# lab2_lyaptsev_buck.net
KiCad netlist of a schematic drawn in Altium Designer
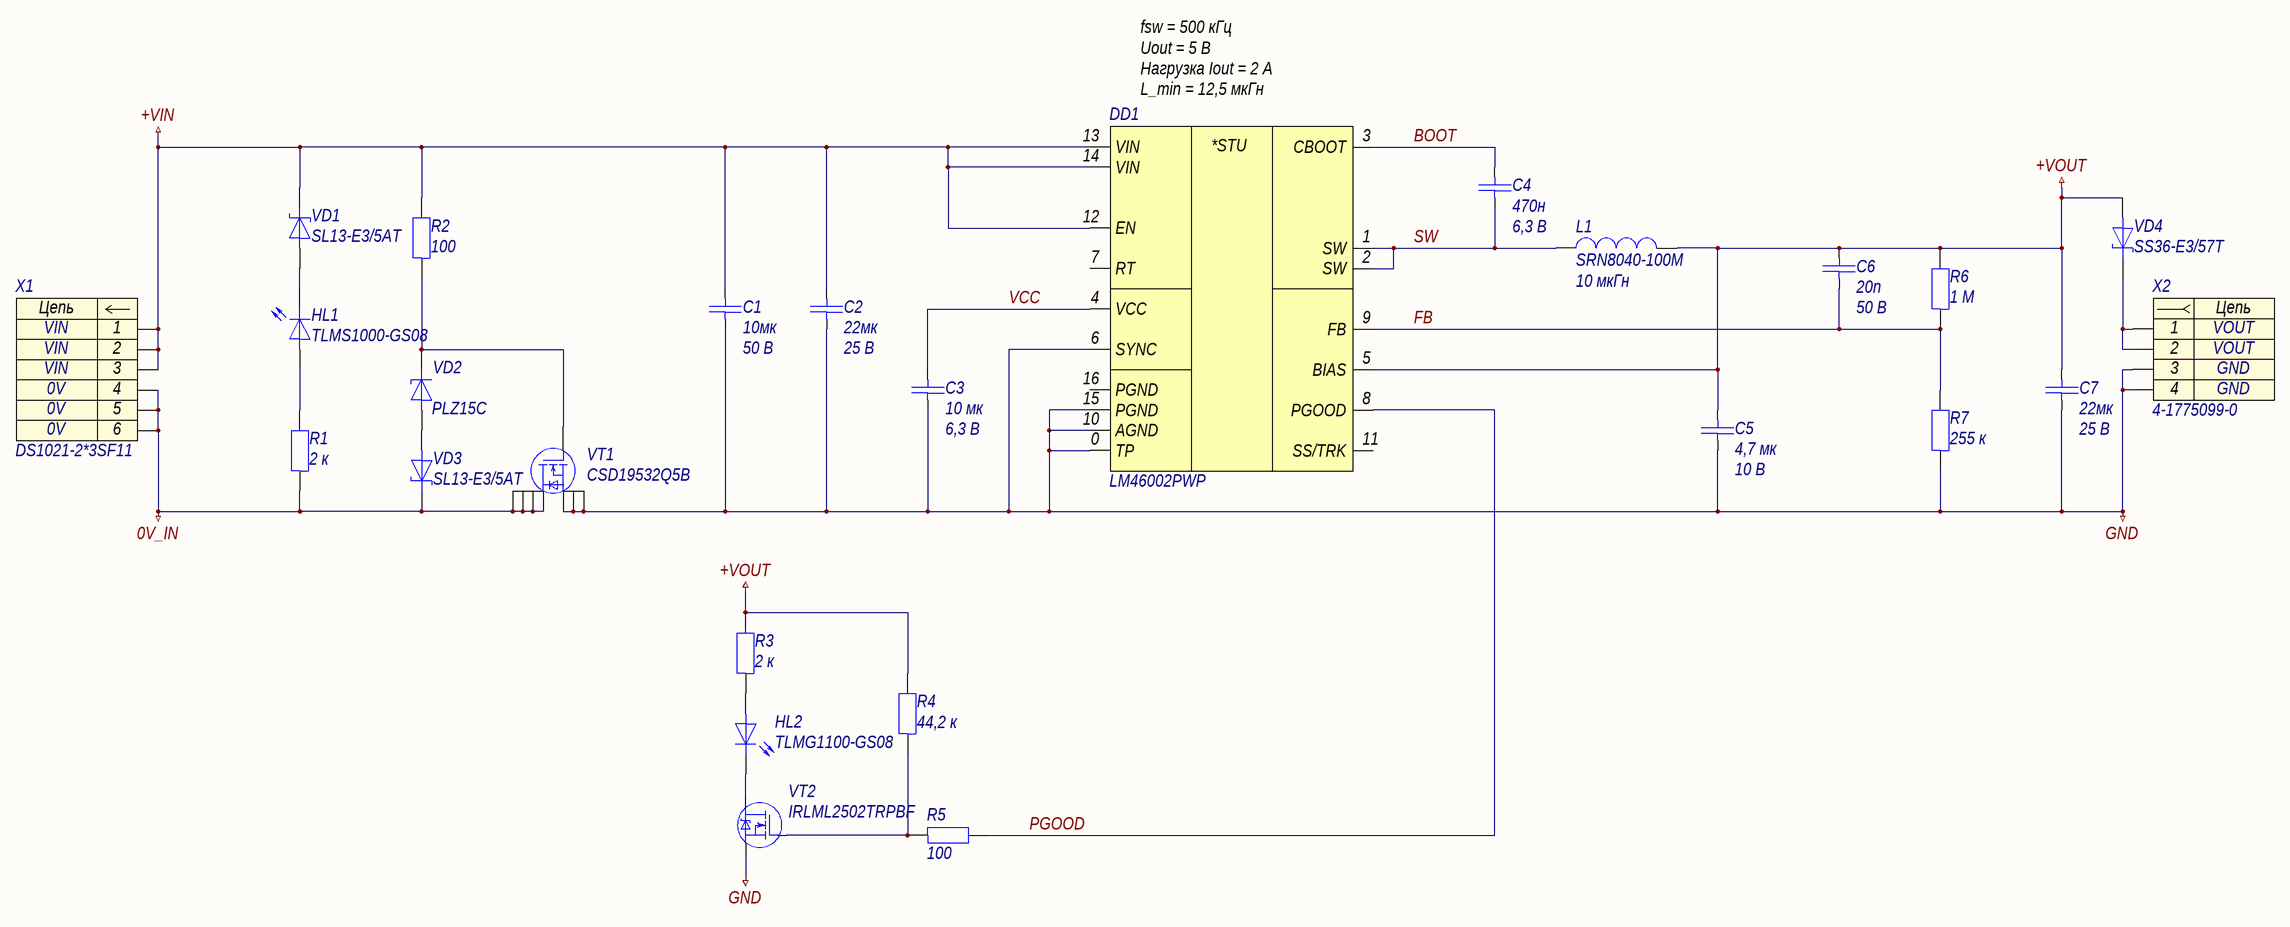
[diagram p0: lab2_lyaptsev_buck.SchDoc]

(export (version "E")
  (design (tool "Eeschema 10.0.6"))
  (components
    (comp (ref "C1")
      (value "10мк")
      (footprint "C1210")
      (description "=Описание")
      (fields (field (name "НАПРЯЖЕНИЕ") "50 В"))
      (libsource (lib "Database_Students_v1") (part "C-NONPOLAR"))
    )
    (comp (ref "C2")
      (value "22мк")
      (footprint "C1210")
      (description "=Описание")
      (fields (field (name "НАПРЯЖЕНИЕ") "25 В"))
      (libsource (lib "Database_Students_v1") (part "C-NONPOLAR"))
    )
    (comp (ref "C3")
      (value "10 мк")
      (footprint "C0603")
      (description "=Описание")
      (fields (field (name "НАПРЯЖЕНИЕ") "6,3 В"))
      (libsource (lib "Database_Students_v1") (part "C-NONPOLAR"))
    )
    (comp (ref "C4")
      (value "470н")
      (footprint "C0402")
      (description "=Описание")
      (fields (field (name "НАПРЯЖЕНИЕ") "6,3 В"))
      (libsource (lib "Database_Students_v1") (part "C-NONPOLAR"))
    )
    (comp (ref "C5")
      (value "4,7 мк")
      (footprint "C0805")
      (description "=Описание")
      (fields (field (name "НАПРЯЖЕНИЕ") "10 В"))
      (libsource (lib "Database_Students_v1") (part "C-NONPOLAR"))
    )
    (comp (ref "C6")
      (value "20п")
      (footprint "C0402")
      (description "=Описание")
      (fields (field (name "НАПРЯЖЕНИЕ") "50 В"))
      (libsource (lib "Database_Students_v1") (part "C-NONPOLAR"))
    )
    (comp (ref "C7")
      (value "22мк")
      (footprint "C1210")
      (description "=Описание")
      (fields (field (name "НАПРЯЖЕНИЕ") "25 В"))
      (libsource (lib "Database_Students_v1") (part "C-NONPOLAR"))
    )
    (comp (ref "DD1")
      (value "LM46002PWP")
      (footprint "HTSSOP-16")
      (description "=Описание")
      (libsource (lib "Database_Students") (part "LM46002PWP"))
    )
    (comp (ref "HL1")
      (value "TLMS1000-GS08")
      (footprint "HL0603")
      (description "=Описание")
      (libsource (lib "Database_Students") (part "HL-COMMON"))
    )
    (comp (ref "HL2")
      (value "TLMG1100-GS08")
      (footprint "HL0603")
      (description "=Описание")
      (libsource (lib "Database_Students") (part "HL-COMMON"))
    )
    (comp (ref "L1")
      (value "SRN8040-100M")
      (footprint "SRN-2-815X790X400")
      (description "=Описание")
      (fields (field (name "ИНДУКТИВНОСТЬ") "10 мкГн"))
      (libsource (lib "Database_Students") (part "INDUCTOR-COMMON"))
    )
    (comp (ref "R1")
      (value "2 к")
      (footprint "R0603")
      (description "=Описание")
      (libsource (lib "Database_Students") (part "R-COMMON"))
    )
    (comp (ref "R2")
      (value "100")
      (footprint "R0603")
      (description "=Описание")
      (libsource (lib "Database_Students") (part "R-COMMON"))
    )
    (comp (ref "R3")
      (value "2 к")
      (footprint "R0603")
      (description "=Описание")
      (libsource (lib "Database_Students") (part "R-COMMON"))
    )
    (comp (ref "R4")
      (value "44,2 к")
      (footprint "R0603")
      (description "=Описание")
      (libsource (lib "Database_Students") (part "R-COMMON"))
    )
    (comp (ref "R5")
      (value "100")
      (footprint "R0603")
      (description "=Описание")
      (libsource (lib "Database_Students") (part "R-COMMON"))
    )
    (comp (ref "R6")
      (value "1 М")
      (footprint "R0603")
      (description "=Описание")
      (libsource (lib "Database_Students") (part "R-COMMON"))
    )
    (comp (ref "R7")
      (value "255 к")
      (footprint "R0603")
      (description "=Описание")
      (libsource (lib "Database_Students") (part "R-COMMON"))
    )
    (comp (ref "VD1")
      (value "SL13-E3/5AT")
      (footprint "DO-214AC")
      (description "=Описание")
      (libsource (lib "Database_Students") (part "DIODE-SCHOTTKY"))
    )
    (comp (ref "VD2")
      (value "PLZ15C")
      (footprint "DO-219AC")
      (description "=Описание")
      (libsource (lib "Database_Students_v1") (part "DO-219AC"))
    )
    (comp (ref "VD3")
      (value "SL13-E3/5AT")
      (footprint "DO-214AC")
      (description "=Описание")
      (libsource (lib "Database_Students") (part "DIODE-SCHOTTKY"))
    )
    (comp (ref "VD4")
      (value "SS36-E3/57T")
      (footprint "DO-214AB")
      (description "=Описание")
      (libsource (lib "Database_Students") (part "DIODE-SCHOTTKY"))
    )
    (comp (ref "VT1")
      (value "CSD19532Q5B")
      (footprint "SON-8")
      (description "=Описание")
      (libsource (lib "Database_Students") (part "TRANSISTOR_7_N"))
    )
    (comp (ref "VT2")
      (value "IRLML2502TRPBF")
      (footprint "SOT-23-3")
      (description "=Описание")
      (libsource (lib "Database_Students") (part "MOSFET-N-1G-1S-1D"))
    )
    (comp (ref "X1")
      (value "DS1021-2*3SF11")
      (footprint "DS1021-2X3SF11")
      (description "=Описание")
      (libsource (lib "Database_Students") (part "HEADER-6-PLG"))
    )
    (comp (ref "X2")
      (value "4-1775099-0")
      (footprint "4-1775099-0")
      (description "=Описание")
      (libsource (lib "Database_Students") (part "HEADER-4-SCT"))
    )
  )
  (nets
    (net (code "1") (name "+VIN") (class "Default")
      (node (ref "C1") (pin "1") (pinfunction "1_1") (pintype "passive"))
      (node (ref "C2") (pin "1") (pinfunction "1_1") (pintype "passive"))
      (node (ref "DD1") (pin "12") (pinfunction "EN_12") (pintype "passive"))
      (node (ref "DD1") (pin "13") (pinfunction "VIN_13") (pintype "passive"))
      (node (ref "DD1") (pin "14") (pinfunction "VIN_14") (pintype "passive"))
      (node (ref "R2") (pin "2") (pinfunction "2_2") (pintype "passive"))
      (node (ref "VD1") (pin "1") (pinfunction "1_1") (pintype "passive"))
      (node (ref "X1") (pin "1") (pinfunction "1_1") (pintype "passive"))
      (node (ref "X1") (pin "2") (pinfunction "2_2") (pintype "passive"))
      (node (ref "X1") (pin "3") (pinfunction "3_3") (pintype "passive"))
    )
    (net (code "2") (name "+VOUT") (class "Default")
      (node (ref "C5") (pin "1") (pinfunction "1_1") (pintype "passive"))
      (node (ref "C6") (pin "1") (pinfunction "1_1") (pintype "passive"))
      (node (ref "C7") (pin "1") (pinfunction "1_1") (pintype "passive"))
      (node (ref "DD1") (pin "5") (pinfunction "BIAS_5") (pintype "passive"))
      (node (ref "L1") (pin "2") (pinfunction "2_2") (pintype "passive"))
      (node (ref "R3") (pin "2") (pinfunction "2_2") (pintype "passive"))
      (node (ref "R4") (pin "2") (pinfunction "2_2") (pintype "passive"))
      (node (ref "R6") (pin "2") (pinfunction "2_2") (pintype "passive"))
      (node (ref "VD4") (pin "2") (pinfunction "2_2") (pintype "passive"))
    )
    (net (code "3") (name "/BOOT") (class "Default")
      (node (ref "C4") (pin "1") (pinfunction "1_1") (pintype "passive"))
      (node (ref "DD1") (pin "3") (pinfunction "CBOOT_3") (pintype "passive"))
    )
    (net (code "4") (name "/FB") (class "Default")
      (node (ref "C6") (pin "2") (pinfunction "2_2") (pintype "passive"))
      (node (ref "DD1") (pin "9") (pinfunction "FB_9") (pintype "passive"))
      (node (ref "R6") (pin "1") (pinfunction "1_1") (pintype "passive"))
      (node (ref "R7") (pin "2") (pinfunction "2_2") (pintype "passive"))
    )
    (net (code "5") (name "/PGOOD") (class "Default")
      (node (ref "DD1") (pin "8") (pinfunction "PGOOD_8") (pintype "passive"))
      (node (ref "R5") (pin "2") (pinfunction "2_2") (pintype "passive"))
    )
    (net (code "6") (name "/SW") (class "Default")
      (node (ref "C4") (pin "2") (pinfunction "2_2") (pintype "passive"))
      (node (ref "DD1") (pin "1") (pinfunction "SW_1") (pintype "passive"))
      (node (ref "DD1") (pin "2") (pinfunction "SW_2") (pintype "passive"))
      (node (ref "L1") (pin "1") (pinfunction "1_1") (pintype "passive"))
    )
    (net (code "7") (name "/VCC") (class "Default")
      (node (ref "C3") (pin "1") (pinfunction "1_1") (pintype "passive"))
      (node (ref "DD1") (pin "4") (pinfunction "VCC_4") (pintype "passive"))
    )
    (net (code "8") (name "0V_IN") (class "Default")
      (node (ref "R1") (pin "1") (pinfunction "1_1") (pintype "passive"))
      (node (ref "VD3") (pin "1") (pinfunction "1_1") (pintype "passive"))
      (node (ref "VT1") (pin "D") (pinfunction "D_D") (pintype "passive"))
      (node (ref "X1") (pin "4") (pinfunction "4_4") (pintype "passive"))
      (node (ref "X1") (pin "5") (pinfunction "5_5") (pintype "passive"))
      (node (ref "X1") (pin "6") (pinfunction "6_6") (pintype "passive"))
    )
    (net (code "9") (name "GND") (class "Default")
      (node (ref "C1") (pin "2") (pinfunction "2_2") (pintype "passive"))
      (node (ref "C2") (pin "2") (pinfunction "2_2") (pintype "passive"))
      (node (ref "C3") (pin "2") (pinfunction "2_2") (pintype "passive"))
      (node (ref "C5") (pin "2") (pinfunction "2_2") (pintype "passive"))
      (node (ref "C7") (pin "2") (pinfunction "2_2") (pintype "passive"))
      (node (ref "DD1") (pin "0") (pinfunction "TP_0") (pintype "passive"))
      (node (ref "DD1") (pin "10") (pinfunction "AGND_10") (pintype "passive"))
      (node (ref "DD1") (pin "15") (pinfunction "PGND_15") (pintype "passive"))
      (node (ref "DD1") (pin "6") (pinfunction "SYNC_6") (pintype "passive"))
      (node (ref "R7") (pin "1") (pinfunction "1_1") (pintype "passive"))
      (node (ref "VT1") (pin "S") (pinfunction "S_S") (pintype "passive"))
      (node (ref "VT2") (pin "S") (pinfunction "S_S") (pintype "passive"))
      (node (ref "X2") (pin "3") (pinfunction "3_3") (pintype "passive"))
      (node (ref "X2") (pin "4") (pinfunction "4_4") (pintype "passive"))
    )
    (net (code "10") (name "Net-(HL1-Pad1)") (class "Default")
      (node (ref "HL1") (pin "1") (pinfunction "1_1") (pintype "passive"))
      (node (ref "VD1") (pin "2") (pinfunction "2_2") (pintype "passive"))
    )
    (net (code "11") (name "Net-(HL1-Pad2)") (class "Default")
      (node (ref "HL1") (pin "2") (pinfunction "2_2") (pintype "passive"))
      (node (ref "R1") (pin "2") (pinfunction "2_2") (pintype "passive"))
    )
    (net (code "12") (name "Net-(HL2-Pad1)") (class "Default")
      (node (ref "HL2") (pin "1") (pinfunction "1_1") (pintype "passive"))
      (node (ref "VT2") (pin "D") (pinfunction "D_D") (pintype "passive"))
    )
    (net (code "13") (name "Net-(HL2-Pad2)") (class "Default")
      (node (ref "HL2") (pin "2") (pinfunction "2_2") (pintype "passive"))
      (node (ref "R3") (pin "1") (pinfunction "1_1") (pintype "passive"))
    )
    (net (code "14") (name "Net-(R2-Pad1)") (class "Default")
      (node (ref "R2") (pin "1") (pinfunction "1_1") (pintype "passive"))
      (node (ref "VD2") (pin "1") (pinfunction "1_1") (pintype "passive"))
      (node (ref "VT1") (pin "G") (pinfunction "G_G") (pintype "passive"))
    )
    (net (code "15") (name "Net-(R4-Pad1)") (class "Default")
      (node (ref "R4") (pin "1") (pinfunction "1_1") (pintype "passive"))
      (node (ref "R5") (pin "1") (pinfunction "1_1") (pintype "passive"))
      (node (ref "VT2") (pin "G") (pinfunction "G_G") (pintype "passive"))
    )
    (net (code "16") (name "Net-(VD2-Pad2)") (class "Default")
      (node (ref "VD2") (pin "2") (pinfunction "2_2") (pintype "passive"))
      (node (ref "VD3") (pin "2") (pinfunction "2_2") (pintype "passive"))
    )
    (net (code "17") (name "Net-(VD4-Pad1)") (class "Default")
      (node (ref "VD4") (pin "1") (pinfunction "1_1") (pintype "passive"))
      (node (ref "X2") (pin "1") (pinfunction "1_1") (pintype "passive"))
      (node (ref "X2") (pin "2") (pinfunction "2_2") (pintype "passive"))
    )
    (net (code "18") (name "unconnected-(DD1-PGND-Pad16)") (class "Default")
      (node (ref "DD1") (pin "16") (pinfunction "PGND_16") (pintype "passive"))
    )
    (net (code "19") (name "unconnected-(DD1-RT-Pad7)") (class "Default")
      (node (ref "DD1") (pin "7") (pinfunction "RT_7") (pintype "passive"))
    )
    (net (code "20") (name "unconnected-(DD1-SS{slash}TRK-Pad11)") (class "Default")
      (node (ref "DD1") (pin "11") (pinfunction "SS/TRK_11") (pintype "passive"))
    )
  )
)
